# usb_adapter.net
KiCad netlist of a schematic drawn in EAGLE
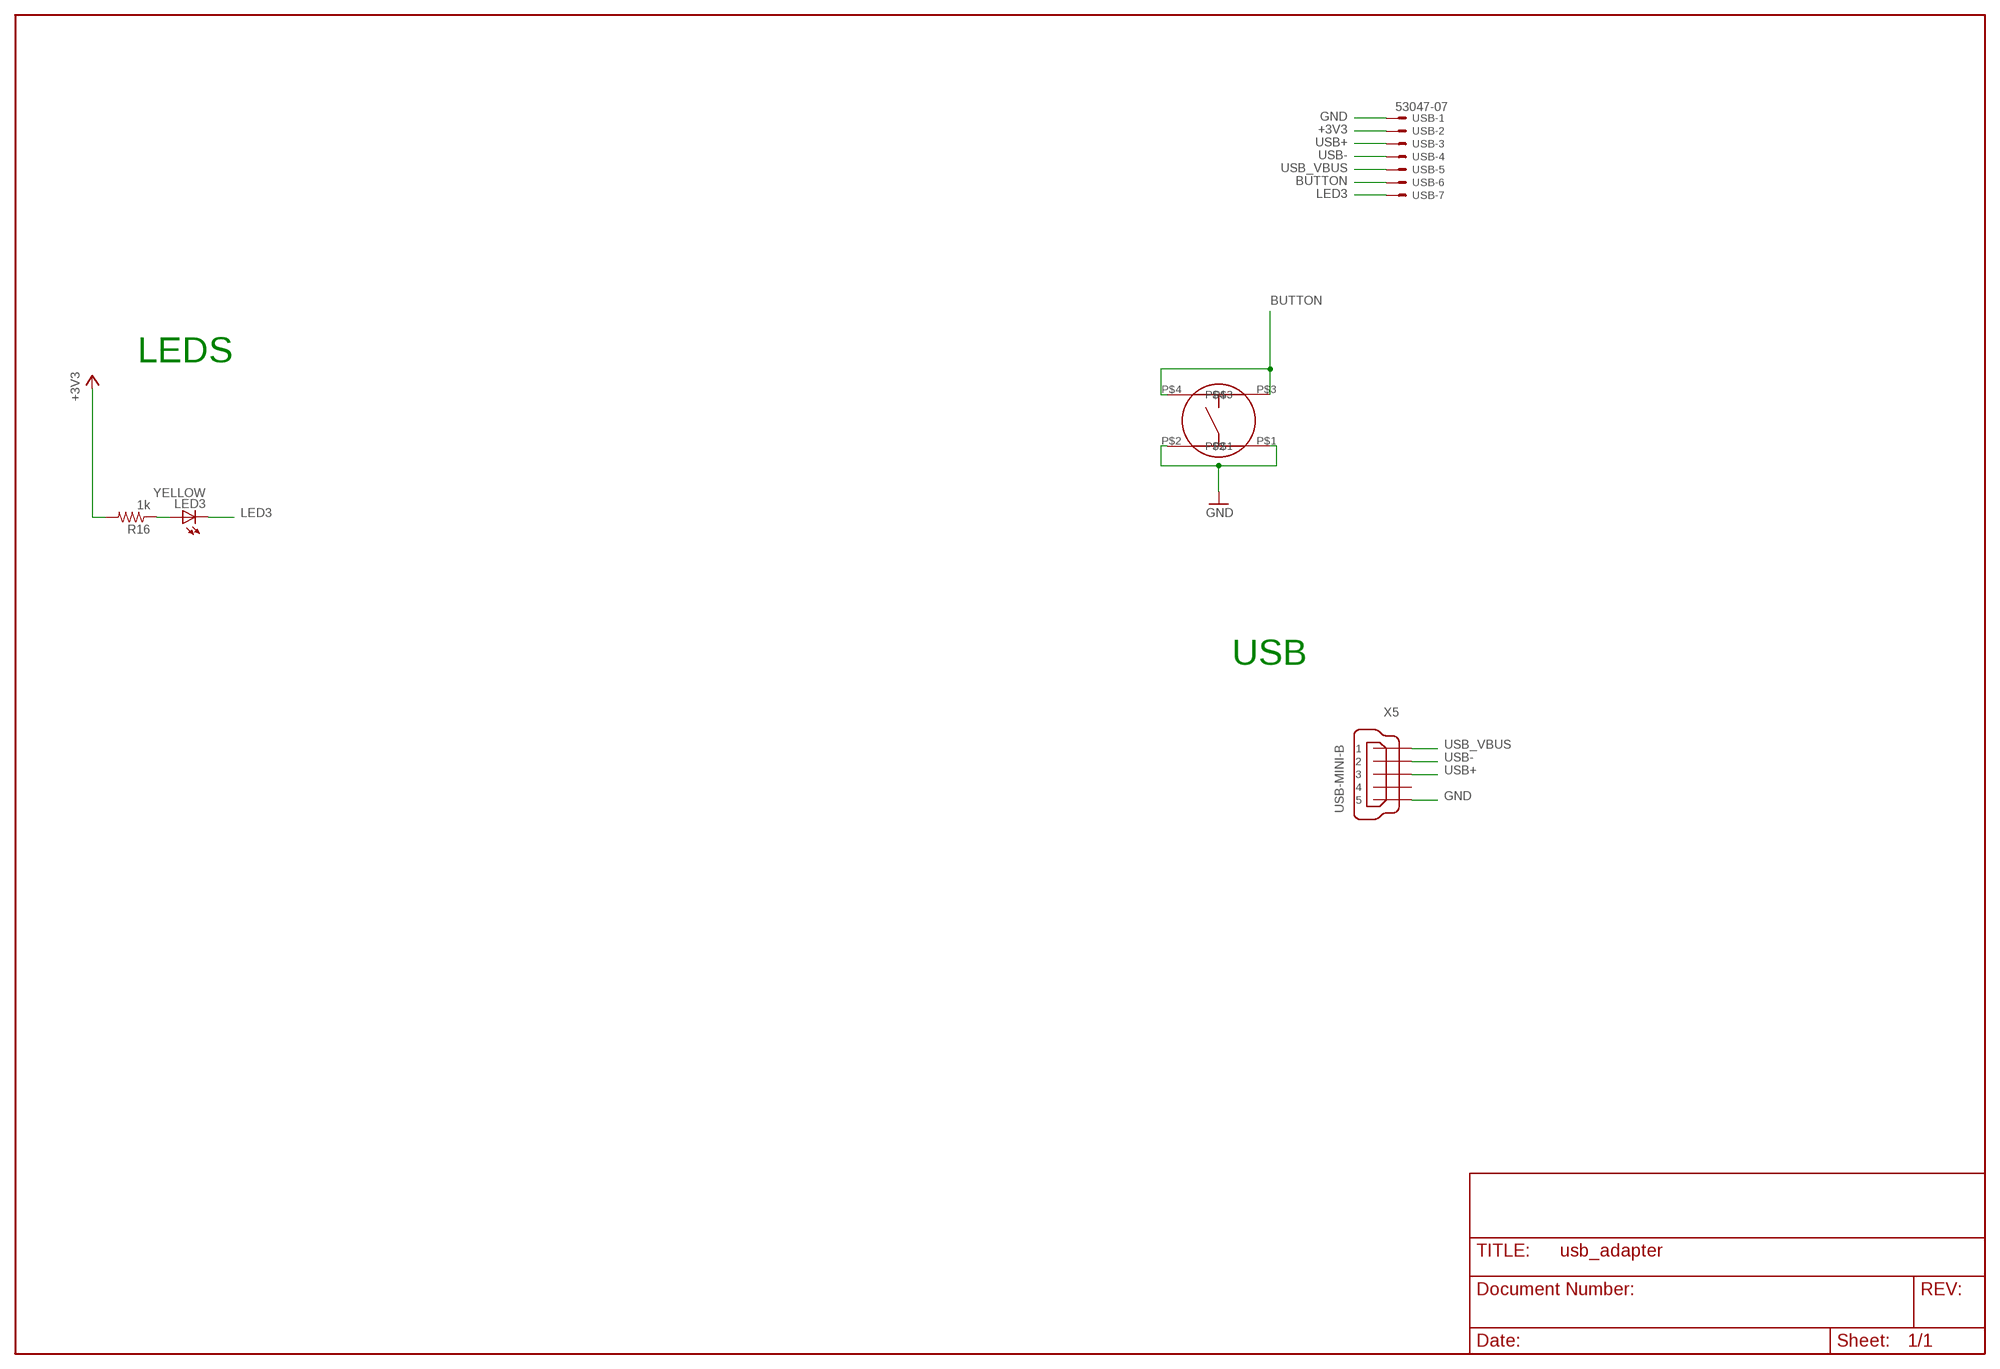
[diagram p0: schematic, sheet 1]

(export (version "E")
  (design (tool "Eeschema 10.0.6"))
  (components
    (comp (ref "LED3")
      (value "YELLOW")
      (footprint "eagle-import:CHIP-LED0805")
      (libsource (lib "eagle-import") (part "LEDCHIP-LED0805"))
    )
    (comp (ref "R16")
      (value "1k")
      (footprint "eagle-import:R0603@1")
      (libsource (lib "eagle-import") (part "R-US_R0603"))
    )
    (comp (ref "SW1")
      (value "B3S")
      (footprint "eagle-import:B3S")
      (libsource (lib "eagle-import") (part "B3S"))
    )
    (comp (ref "USB")
      (value "53047-07")
      (footprint "eagle-import:53047-07")
      (libsource (lib "eagle-import") (part "53?-07047"))
    )
    (comp (ref "X5")
      (value "USB-MINI-B")
      (footprint "eagle-import:UX60-MB-5ST")
      (libsource (lib "eagle-import") (part "MINI-USB-UX60-MB-5ST"))
    )
  )
  (nets
    (net (code "1") (name "+3V3") (class "Default")
      (node (ref "R16") (pin "2") (pinfunction "2_2") (pintype "passive"))
      (node (ref "USB") (pin "2") (pinfunction "S_2") (pintype "passive"))
    )
    (net (code "2") (name "/BUTTON") (class "Default")
      (node (ref "SW1") (pin "P$3") (pinfunction "P$3_P$3") (pintype "bidirectional"))
      (node (ref "SW1") (pin "P$4") (pinfunction "P$4_P$4") (pintype "bidirectional"))
      (node (ref "USB") (pin "6") (pinfunction "S_6") (pintype "passive"))
    )
    (net (code "3") (name "/LED3") (class "Default")
      (node (ref "LED3") (pin "C") (pinfunction "C_C") (pintype "passive"))
      (node (ref "USB") (pin "7") (pinfunction "S_7") (pintype "passive"))
    )
    (net (code "4") (name "/USB+") (class "Default")
      (node (ref "USB") (pin "3") (pinfunction "S_3") (pintype "passive"))
      (node (ref "X5") (pin "3") (pinfunction "3_3") (pintype "input"))
    )
    (net (code "5") (name "/USB-") (class "Default")
      (node (ref "USB") (pin "4") (pinfunction "S_4") (pintype "passive"))
      (node (ref "X5") (pin "2") (pinfunction "2_2") (pintype "input"))
    )
    (net (code "6") (name "/USB_VBUS") (class "Default")
      (node (ref "USB") (pin "5") (pinfunction "S_5") (pintype "passive"))
      (node (ref "X5") (pin "1") (pinfunction "1_1") (pintype "input"))
    )
    (net (code "7") (name "GND") (class "Default")
      (node (ref "SW1") (pin "P$1") (pinfunction "P$1_P$1") (pintype "bidirectional"))
      (node (ref "SW1") (pin "P$2") (pinfunction "P$2_P$2") (pintype "bidirectional"))
      (node (ref "USB") (pin "1") (pinfunction "S_1") (pintype "passive"))
      (node (ref "X5") (pin "5") (pinfunction "5_5") (pintype "input"))
    )
    (net (code "8") (name "Net-(LED3-PadA)") (class "Default")
      (node (ref "LED3") (pin "A") (pinfunction "A_A") (pintype "passive"))
      (node (ref "R16") (pin "1") (pinfunction "1_1") (pintype "passive"))
    )
    (net (code "9") (name "unconnected-(X5-Pad4)") (class "Default")
      (node (ref "X5") (pin "4") (pinfunction "4_4") (pintype "input"))
    )
  )
)
